# Flyback.net
KiCad netlist of a schematic drawn in EasyEDA Pro
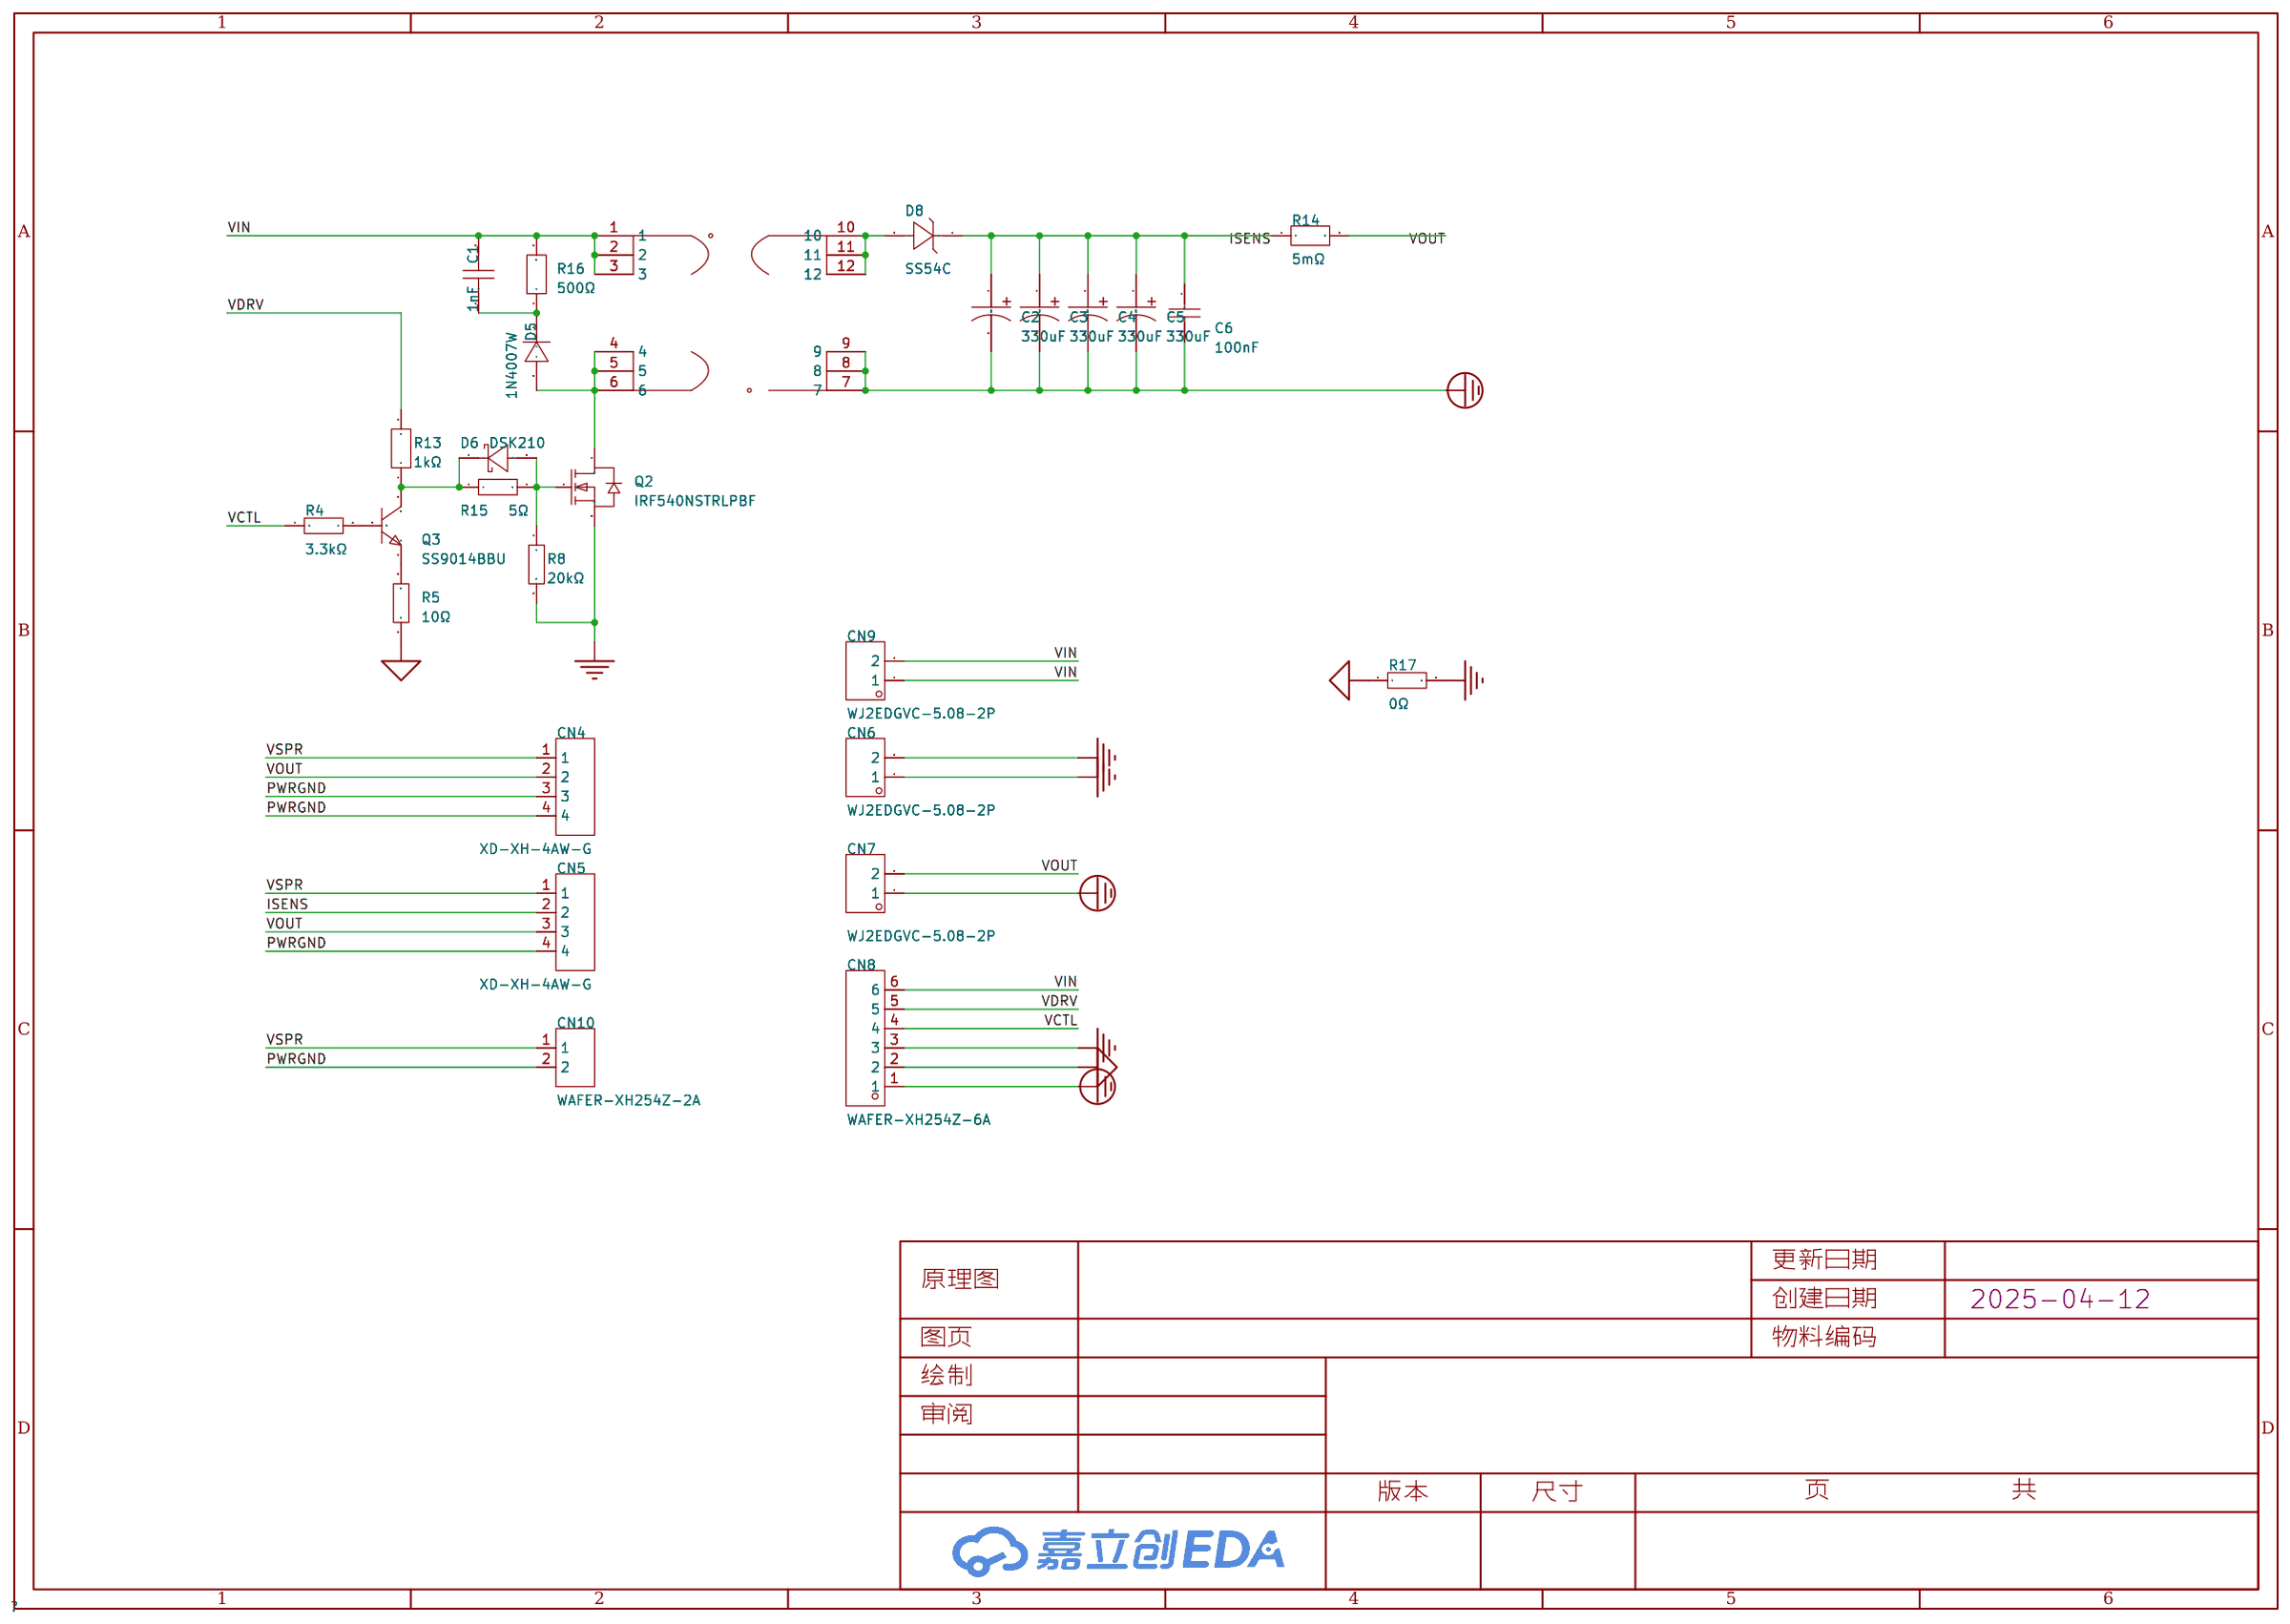
[diagram p0: schematic sheet]

(export (version "E")
  (design (tool "Eeschema 10.0.6"))
  (components
    (comp (ref "C1")
      (value "1nF")
      (footprint "easyedapro:C0805")
      (description "容值:1nF;精度:±10%;额定电压:50V;材质(温度系数):X7R;")
      (fields
        (field (name "Manufacturer Part") "CC0805KRX7R9BB102")
        (field (name "Manufacturer") "YAGEO(国巨)")
      )
      (libsource (lib "easyedapro") (part "CC0805KRX7R9BB102"))
    )
    (comp (ref "C2")
      (value "330uF")
      (footprint "easyedapro:CAP-TH_BD12.5-P5.00-D0.6-FD")
      (description "容值:330uF;精度:±20%;额定电压:80V;纹波电流:1.368A@100kHz;等效串联电阻:94mΩ@100kHz;")
      (fields (field (name "Manufacturer Part") "LKML1601K331MF") (field (name "Manufacturer") "Ymin(永铭)"))
      (libsource (lib "easyedapro") (part "LKML1601K331MF"))
    )
    (comp (ref "C3")
      (value "330uF")
      (footprint "easyedapro:CAP-TH_BD12.5-P5.00-D0.6-FD")
      (description "容值:330uF;精度:±20%;额定电压:80V;纹波电流:1.368A@100kHz;等效串联电阻:94mΩ@100kHz;")
      (fields (field (name "Manufacturer Part") "LKML1601K331MF") (field (name "Manufacturer") "Ymin(永铭)"))
      (libsource (lib "easyedapro") (part "LKML1601K331MF"))
    )
    (comp (ref "C4")
      (value "330uF")
      (footprint "easyedapro:CAP-TH_BD12.5-P5.00-D0.6-FD")
      (description "容值:330uF;精度:±20%;额定电压:80V;纹波电流:1.368A@100kHz;等效串联电阻:94mΩ@100kHz;")
      (fields (field (name "Manufacturer Part") "LKML1601K331MF") (field (name "Manufacturer") "Ymin(永铭)"))
      (libsource (lib "easyedapro") (part "LKML1601K331MF"))
    )
    (comp (ref "C5")
      (value "330uF")
      (footprint "easyedapro:CAP-TH_BD12.5-P5.00-D0.6-FD")
      (description "容值:330uF;精度:±20%;额定电压:80V;纹波电流:1.368A@100kHz;等效串联电阻:94mΩ@100kHz;")
      (fields (field (name "Manufacturer Part") "LKML1601K331MF") (field (name "Manufacturer") "Ymin(永铭)"))
      (libsource (lib "easyedapro") (part "LKML1601K331MF"))
    )
    (comp (ref "C6")
      (value "100nF")
      (footprint "easyedapro:C0805")
      (description "容值:100nF;精度:±10%;额定电压:100V;材质(温度系数):X7R;")
      (fields
        (field (name "Manufacturer Part") "CL21B104KCFNNNE")
        (field (name "Manufacturer") "SAMSUNG(三星)")
      )
      (libsource (lib "easyedapro") (part "CL21B104KCFNNNE"))
    )
    (comp (ref "CN4")
      (value "XD-XH-4AW-G")
      (footprint "easyedapro:CONN-TH_XD-XH-4AW-G")
      (description "插针结构:1x4P;间距:2.54mm;安装方式:弯插;参考系列:XH;总PIN数:4P;排数:1;每排PIN数:4;行距:2.54mm;额定电流:3A;工作温度:-25°C~+85°C;")
      (fields (field (name "Manufacturer") "XUNDA(讯答)"))
      (libsource (lib "easyedapro") (part "XD-XH-4AW-G"))
    )
    (comp (ref "CN5")
      (value "XD-XH-4AW-G")
      (footprint "easyedapro:CONN-TH_XD-XH-4AW-G")
      (description "插针结构:1x4P;间距:2.54mm;安装方式:弯插;参考系列:XH;总PIN数:4P;排数:1;每排PIN数:4;行距:2.54mm;额定电流:3A;工作温度:-25°C~+85°C;")
      (fields (field (name "Manufacturer") "XUNDA(讯答)"))
      (libsource (lib "easyedapro") (part "XD-XH-4AW-G"))
    )
    (comp (ref "CN6")
      (value "WJ2EDGVC-5.08-2P")
      (footprint "easyedapro:CONN-TH_WJ2EDGVC-5.08-2P")
      (fields (field (name "Manufacturer") "KANGNEX(康奈克斯电气)"))
      (libsource (lib "easyedapro") (part "WJ2EDGVC-5.08-2P"))
    )
    (comp (ref "CN7")
      (value "WJ2EDGVC-5.08-2P")
      (footprint "easyedapro:CONN-TH_WJ2EDGVC-5.08-2P")
      (fields (field (name "Manufacturer") "KANGNEX(康奈克斯电气)"))
      (libsource (lib "easyedapro") (part "WJ2EDGVC-5.08-2P"))
    )
    (comp (ref "CN8")
      (value "WAFER-XH254Z-6A")
      (footprint "easyedapro:CONN-TH_XH2.54-6P")
      (description "插针结构:1x6P;间距:2.54mm;安装方式:直插;参考系列:XH;总PIN数:6P;排数:1;每排PIN数:6;额定电流:3A;工作温度范围:-25°C~+85°C;")
      (fields (field (name "Manufacturer") "HANBO(汉博)"))
      (libsource (lib "easyedapro") (part "WAFER-XH254Z-6A"))
    )
    (comp (ref "CN9")
      (value "WJ2EDGVC-5.08-2P")
      (footprint "easyedapro:CONN-TH_WJ2EDGVC-5.08-2P")
      (fields (field (name "Manufacturer") "KANGNEX(康奈克斯电气)"))
      (libsource (lib "easyedapro") (part "WJ2EDGVC-5.08-2P"))
    )
    (comp (ref "CN10")
      (value "WAFER-XH254Z-2A")
      (footprint "easyedapro:CONN-TH_2P-P2.50_XH-2A_3045048")
      (description "插针结构:1x2P;间距:2.54mm;安装方式:直插;参考系列:XH;总PIN数:2P;排数:1;每排PIN数:2;额定电流:3A;工作温度范围:-25°C~+85°C;")
      (fields (field (name "Manufacturer") "HANBO(汉博)"))
      (libsource (lib "easyedapro") (part "WAFER-XH254Z-2A"))
    )
    (comp (ref "D5")
      (value "1N4007W")
      (footprint "easyedapro:SOD-123FL_L2.7-W1.8-LS3.8-RD")
      (description "二极管配置:独立式;正向压降(Vf):1V@1.0A;直流反向耐压(Vr):1kV;整流电流:1A;")
      (fields (field (name "Manufacturer") "宏迦橙"))
      (libsource (lib "easyedapro") (part "1N4007W_C18199088"))
    )
    (comp (ref "D6")
      (value "DSK210")
      (footprint "easyedapro:SOD-123FL_L2.7-W1.8-LS3.8-RD")
      (description "二极管配置:独立式;正向压降(Vf):850mV@2A;直流反向耐压(Vr):100V;整流电流:2A;")
      (fields (field (name "Manufacturer") "宏迦橙"))
      (libsource (lib "easyedapro") (part "DSK210_C7502713"))
    )
    (comp (ref "D8")
      (value "SS54C")
      (footprint "easyedapro:SMC_L6.9-W5.9-LS7.9-RD")
      (description "二极管配置:独立式;正向压降(Vf):-;直流反向耐压(Vr):40V;整流电流:5A;")
      (fields (field (name "Manufacturer") "宏嘉诚"))
      (libsource (lib "easyedapro") (part "SS54C_C18199188"))
    )
    (comp (ref "Q2")
      (value "IRF540NSTRLPBF")
      (footprint "easyedapro:TO-263-2_L10.0-W9.1-P5.08-LS15.2-TL")
      (fields (field (name "Manufacturer") "Infineon(英飞凌)"))
      (libsource (lib "easyedapro") (part "IRF540NSTRLPBF"))
    )
    (comp (ref "Q3")
      (value "SS9014BBU")
      (footprint "easyedapro:TO-92-3_L4.8-W3.7-P1.27-L-1")
      (description "晶体管类型:NPN;集电极电流(Ic):100mA;集射极击穿电压(Vceo):45V;耗散功率(Pd):450mW;直流电流增益(hFE):100@1mA,5V;")
      (fields (field (name "Manufacturer") "onsemi(安森美)"))
      (libsource (lib "easyedapro") (part "SS9014BBU"))
    )
    (comp (ref "R4")
      (value "3.3kΩ")
      (footprint "easyedapro:R0805")
      (description "电阻类型:厚膜电阻;阻值:3.3kΩ;精度:±1%;功率:125mW;最大工作电压:150V;温度系数:±100ppm/°C;")
      (fields
        (field (name "Manufacturer Part") "0805W8F3301T5E")
        (field (name "Manufacturer") "UNI-ROYAL(厚声)")
      )
      (libsource (lib "easyedapro") (part "0805W8F3301T5E"))
    )
    (comp (ref "R5")
      (value "10Ω")
      (footprint "easyedapro:R1206")
      (description "电阻类型:厚膜电阻;阻值:10Ω;精度:±1%;功率:250mW;最大工作电压:200V;温度系数:±400ppm/°C;")
      (fields
        (field (name "Manufacturer Part") "1206W4F100JT5E")
        (field (name "Manufacturer") "UNI-ROYAL(厚声)")
      )
      (libsource (lib "easyedapro") (part "1206W4F100JT5E"))
    )
    (comp (ref "R8")
      (value "20kΩ")
      (footprint "easyedapro:R0805")
      (description "电阻类型:厚膜电阻;阻值:20kΩ;精度:±1%;功率:125mW;最大工作电压:150V;温度系数:±100ppm/°C;")
      (fields
        (field (name "Manufacturer Part") "0805W8F2002T5E")
        (field (name "Manufacturer") "UNI-ROYAL(厚声)")
      )
      (libsource (lib "easyedapro") (part "0805W8F2002T5E"))
    )
    (comp (ref "R13")
      (value "1kΩ")
      (footprint "easyedapro:R0805")
      (description "电阻类型:-;阻值:1kΩ;精度:±0.01%;功率:200mW;温度系数:±0.2ppm/°C;")
      (fields
        (field (name "Manufacturer Part") "Y16241K00000T24R")
        (field (name "Manufacturer") "VISHAY(威世)")
      )
      (libsource (lib "easyedapro") (part "Y16241K00000T24R"))
    )
    (comp (ref "R14")
      (value "5mΩ")
      (footprint "easyedapro:RES-SMD_L6.4-W3.2-1")
      (description "电阻类型:采样电阻;阻值:5mΩ;精度:±1%;功率:3W;安装方式:贴片;")
      (fields
        (field (name "Manufacturer Part") "HoJLR2512-3W-5mR-1%")
        (field (name "Manufacturer") "Milliohm(毫欧)")
      )
      (libsource (lib "easyedapro") (part "HOJLR2512-3W-5MR-1%"))
    )
    (comp (ref "R15")
      (value "5Ω")
      (footprint "easyedapro:R0805_NEW")
      (description "电阻类型:厚膜电阻;阻值:10Ω;精度:±1%;功率:125mW;最大工作电压:150V;温度系数:±200ppm/°C;")
      (fields
        (field (name "Manufacturer Part") "0805W8F100JT5E")
        (field (name "Manufacturer") "UNI-ROYAL(厚声)")
      )
      (libsource (lib "easyedapro") (part "0805W8F100JT5E"))
    )
    (comp (ref "R16")
      (value "500Ω")
      (footprint "easyedapro:R0805")
      (description "电阻类型:薄膜电阻;阻值:500Ω;精度:±1%;功率:125mW;最大工作电压:150V;温度系数:±25ppm/°C;")
      (fields (field (name "Manufacturer Part") "ARG05FTC5000") (field (name "Manufacturer") "Viking(光颉)"))
      (libsource (lib "easyedapro") (part "ARG05FTC5000"))
    )
    (comp (ref "R17")
      (value "0Ω")
      (footprint "easyedapro:R0805")
      (description "电阻类型:厚膜电阻;阻值:0Ω;精度:±1%;功率:125mW;最大工作电压:150V;温度系数:±800ppm/°C;")
      (fields
        (field (name "Manufacturer Part") "0805W8F0000T5E")
        (field (name "Manufacturer") "UNI-ROYAL(厚声)")
      )
      (libsource (lib "easyedapro") (part "0805W8F0000T5E"))
    )
    (comp (ref "T1")
      (value "~")
      (footprint "easyedapro:PQ3220")
      (libsource (lib "easyedapro") (part "Flyback19{colon}3"))
    )
  )
  (nets
    (net (code "1") (name "/ISENS") (class "Default")
      (node (ref "C2") (pin "1") (pinfunction "1_1") (pintype "unspecified"))
      (node (ref "C3") (pin "1") (pinfunction "1_1") (pintype "unspecified"))
      (node (ref "C4") (pin "1") (pinfunction "1_1") (pintype "unspecified"))
      (node (ref "C5") (pin "1") (pinfunction "1_1") (pintype "unspecified"))
      (node (ref "C6") (pin "1") (pinfunction "1_1") (pintype "input"))
      (node (ref "CN5") (pin "2") (pinfunction "2_2") (pintype "unspecified"))
      (node (ref "D8") (pin "1") (pinfunction "K_1") (pintype "unspecified"))
      (node (ref "R14") (pin "1") (pinfunction "1_1") (pintype "unspecified"))
    )
    (net (code "2") (name "/VCTL") (class "Default")
      (node (ref "CN8") (pin "4") (pinfunction "4_4") (pintype "unspecified"))
      (node (ref "R4") (pin "1") (pinfunction "1_1") (pintype "input"))
    )
    (net (code "3") (name "/VDRV") (class "Default")
      (node (ref "CN8") (pin "5") (pinfunction "5_5") (pintype "unspecified"))
      (node (ref "R13") (pin "2") (pinfunction "2_2") (pintype "unspecified"))
    )
    (net (code "4") (name "/VIN") (class "Default")
      (node (ref "C1") (pin "2") (pinfunction "2_2") (pintype "unspecified"))
      (node (ref "CN8") (pin "6") (pinfunction "6_6") (pintype "unspecified"))
      (node (ref "CN9") (pin "1") (pinfunction "1_1") (pintype "unspecified"))
      (node (ref "CN9") (pin "2") (pinfunction "2_2") (pintype "unspecified"))
      (node (ref "R16") (pin "2") (pinfunction "2_2") (pintype "unspecified"))
      (node (ref "T1") (pin "1") (pinfunction "1_1") (pintype "input"))
      (node (ref "T1") (pin "2") (pinfunction "2_2") (pintype "input"))
      (node (ref "T1") (pin "3") (pinfunction "3_3") (pintype "input"))
    )
    (net (code "5") (name "/VOUT") (class "Default")
      (node (ref "CN4") (pin "2") (pinfunction "2_2") (pintype "unspecified"))
      (node (ref "CN5") (pin "3") (pinfunction "3_3") (pintype "unspecified"))
      (node (ref "CN7") (pin "2") (pinfunction "2_2") (pintype "unspecified"))
      (node (ref "R14") (pin "2") (pinfunction "2_2") (pintype "unspecified"))
    )
    (net (code "6") (name "/VSPR") (class "Default")
      (node (ref "CN10") (pin "1") (pinfunction "1_1") (pintype "unspecified"))
      (node (ref "CN4") (pin "1") (pinfunction "1_1") (pintype "unspecified"))
      (node (ref "CN5") (pin "1") (pinfunction "1_1") (pintype "unspecified"))
    )
    (net (code "7") (name "AGND") (class "Default")
      (node (ref "CN8") (pin "2") (pinfunction "2_2") (pintype "unspecified"))
      (node (ref "R17") (pin "1") (pinfunction "1_1") (pintype "input"))
      (node (ref "R5") (pin "1") (pinfunction "1_1") (pintype "input"))
    )
    (net (code "8") (name "GND") (class "Default")
      (node (ref "CN6") (pin "1") (pinfunction "1_1") (pintype "unspecified"))
      (node (ref "CN6") (pin "2") (pinfunction "2_2") (pintype "unspecified"))
      (node (ref "CN8") (pin "3") (pinfunction "3_3") (pintype "unspecified"))
      (node (ref "Q2") (pin "3") (pinfunction "S_3") (pintype "unspecified"))
      (node (ref "R17") (pin "2") (pinfunction "2_2") (pintype "input"))
      (node (ref "R8") (pin "2") (pinfunction "2_2") (pintype "input"))
    )
    (net (code "9") (name "Net-(D5-A)") (class "Default")
      (node (ref "D5") (pin "2") (pinfunction "A_2") (pintype "unspecified"))
      (node (ref "Q2") (pin "4") (pinfunction "D_4") (pintype "unspecified"))
      (node (ref "T1") (pin "4") (pinfunction "4_4") (pintype "input"))
      (node (ref "T1") (pin "5") (pinfunction "5_5") (pintype "input"))
      (node (ref "T1") (pin "6") (pinfunction "6_6") (pintype "input"))
    )
    (net (code "10") (name "Net-(D5-K)") (class "Default")
      (node (ref "C1") (pin "1") (pinfunction "1_1") (pintype "unspecified"))
      (node (ref "D5") (pin "1") (pinfunction "K_1") (pintype "unspecified"))
      (node (ref "R16") (pin "1") (pinfunction "1_1") (pintype "unspecified"))
    )
    (net (code "11") (name "Net-(D6-A)") (class "Default")
      (node (ref "D6") (pin "2") (pinfunction "A_2") (pintype "unspecified"))
      (node (ref "Q2") (pin "1") (pinfunction "G_1") (pintype "unspecified"))
      (node (ref "R15") (pin "2") (pinfunction "2_2") (pintype "input"))
      (node (ref "R8") (pin "1") (pinfunction "1_1") (pintype "input"))
    )
    (net (code "12") (name "Net-(D6-K)") (class "Default")
      (node (ref "D6") (pin "1") (pinfunction "K_1") (pintype "unspecified"))
      (node (ref "Q3") (pin "3") (pinfunction "C_3") (pintype "unspecified"))
      (node (ref "R13") (pin "1") (pinfunction "1_1") (pintype "unspecified"))
      (node (ref "R15") (pin "1") (pinfunction "1_1") (pintype "input"))
    )
    (net (code "13") (name "Net-(D8-A)") (class "Default")
      (node (ref "D8") (pin "2") (pinfunction "A_2") (pintype "unspecified"))
      (node (ref "T1") (pin "10") (pinfunction "10_10") (pintype "input"))
      (node (ref "T1") (pin "11") (pinfunction "11_11") (pintype "input"))
      (node (ref "T1") (pin "12") (pinfunction "12_12") (pintype "input"))
    )
    (net (code "14") (name "Net-(Q3-B)") (class "Default")
      (node (ref "Q3") (pin "2") (pinfunction "B_2") (pintype "unspecified"))
      (node (ref "R4") (pin "2") (pinfunction "2_2") (pintype "input"))
    )
    (net (code "15") (name "Net-(Q3-E)") (class "Default")
      (node (ref "Q3") (pin "1") (pinfunction "E_1") (pintype "unspecified"))
      (node (ref "R5") (pin "2") (pinfunction "2_2") (pintype "input"))
    )
    (net (code "16") (name "PWRGND") (class "Default")
      (node (ref "C2") (pin "2") (pinfunction "2_2") (pintype "unspecified"))
      (node (ref "C3") (pin "2") (pinfunction "2_2") (pintype "unspecified"))
      (node (ref "C4") (pin "2") (pinfunction "2_2") (pintype "unspecified"))
      (node (ref "C5") (pin "2") (pinfunction "2_2") (pintype "unspecified"))
      (node (ref "C6") (pin "2") (pinfunction "2_2") (pintype "input"))
      (node (ref "CN10") (pin "2") (pinfunction "2_2") (pintype "unspecified"))
      (node (ref "CN4") (pin "3") (pinfunction "3_3") (pintype "unspecified"))
      (node (ref "CN4") (pin "4") (pinfunction "4_4") (pintype "unspecified"))
      (node (ref "CN5") (pin "4") (pinfunction "4_4") (pintype "unspecified"))
      (node (ref "CN7") (pin "1") (pinfunction "1_1") (pintype "unspecified"))
      (node (ref "CN8") (pin "1") (pinfunction "1_1") (pintype "unspecified"))
      (node (ref "T1") (pin "7") (pinfunction "7_7") (pintype "input"))
      (node (ref "T1") (pin "8") (pinfunction "8_8") (pintype "input"))
      (node (ref "T1") (pin "9") (pinfunction "9_9") (pintype "input"))
    )
  )
)
